# sch.net
KiCad netlist of a schematic drawn in Altium Designer
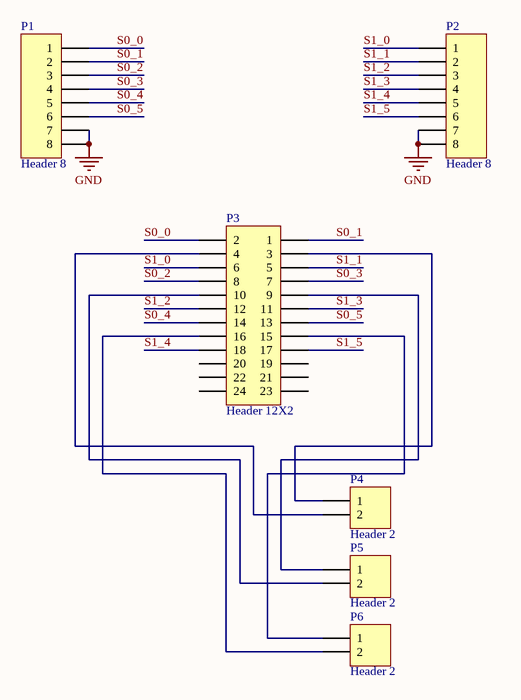
[diagram p0: sch.SchDoc]

(export (version "E")
  (design (tool "Eeschema 10.0.6"))
  (components
    (comp (ref "P1")
      (value "Header 8")
      (footprint "DS1102")
      (description "Header, 8-Pin")
      (fields (field (name "PUBLISHER") "Altium Limited"))
      (libsource (lib "Miscellaneous Connectors") (part "Header 8"))
    )
    (comp (ref "P2")
      (value "Header 8")
      (footprint "DS1102")
      (description "Header, 8-Pin")
      (fields (field (name "PUBLISHER") "Altium Limited"))
      (libsource (lib "") (part "Header 8_1"))
    )
    (comp (ref "P3")
      (value "Header 12X2")
      (footprint "P2K-8")
      (description "Header, 12-Pin, Dual row")
      (fields (field (name "PUBLISHER") "Altium Limited"))
      (libsource (lib "Miscellaneous Connectors") (part "Header 12X2"))
    )
    (comp (ref "P4")
      (value "Header 2")
      (footprint "HDR1X2")
      (description "Header, 2-Pin")
      (fields (field (name "PUBLISHER") "Altium Limited"))
      (libsource (lib "Miscellaneous Connectors") (part "Header 2"))
    )
    (comp (ref "P5")
      (value "Header 2")
      (footprint "HDR1X2")
      (description "Header, 2-Pin")
      (fields (field (name "PUBLISHER") "Altium Limited"))
      (libsource (lib "Miscellaneous Connectors") (part "Header 2"))
    )
    (comp (ref "P6")
      (value "Header 2")
      (footprint "HDR1X2")
      (description "Header, 2-Pin")
      (fields (field (name "PUBLISHER") "Altium Limited"))
      (libsource (lib "Miscellaneous Connectors") (part "Header 2"))
    )
  )
  (nets
    (net (code "1") (name "/S0_0") (class "Default")
      (node (ref "P1") (pin "1") (pinfunction "1_1") (pintype "passive"))
      (node (ref "P3") (pin "2") (pinfunction "2_2") (pintype "passive"))
    )
    (net (code "2") (name "/S0_1") (class "Default")
      (node (ref "P1") (pin "2") (pinfunction "2_2") (pintype "passive"))
      (node (ref "P3") (pin "1") (pinfunction "1_1") (pintype "passive"))
    )
    (net (code "3") (name "/S0_2") (class "Default")
      (node (ref "P1") (pin "3") (pinfunction "3_3") (pintype "passive"))
      (node (ref "P3") (pin "8") (pinfunction "8_8") (pintype "passive"))
    )
    (net (code "4") (name "/S0_3") (class "Default")
      (node (ref "P1") (pin "4") (pinfunction "4_4") (pintype "passive"))
      (node (ref "P3") (pin "7") (pinfunction "7_7") (pintype "passive"))
    )
    (net (code "5") (name "/S0_4") (class "Default")
      (node (ref "P1") (pin "5") (pinfunction "5_5") (pintype "passive"))
      (node (ref "P3") (pin "14") (pinfunction "14_14") (pintype "passive"))
    )
    (net (code "6") (name "/S0_5") (class "Default")
      (node (ref "P1") (pin "6") (pinfunction "6_6") (pintype "passive"))
      (node (ref "P3") (pin "13") (pinfunction "13_13") (pintype "passive"))
    )
    (net (code "7") (name "/S1_0") (class "Default")
      (node (ref "P2") (pin "1") (pinfunction "1_1") (pintype "passive"))
      (node (ref "P3") (pin "6") (pinfunction "6_6") (pintype "passive"))
    )
    (net (code "8") (name "/S1_1") (class "Default")
      (node (ref "P2") (pin "2") (pinfunction "2_2") (pintype "passive"))
      (node (ref "P3") (pin "5") (pinfunction "5_5") (pintype "passive"))
    )
    (net (code "9") (name "/S1_2") (class "Default")
      (node (ref "P2") (pin "3") (pinfunction "3_3") (pintype "passive"))
      (node (ref "P3") (pin "12") (pinfunction "12_12") (pintype "passive"))
    )
    (net (code "10") (name "/S1_3") (class "Default")
      (node (ref "P2") (pin "4") (pinfunction "4_4") (pintype "passive"))
      (node (ref "P3") (pin "11") (pinfunction "11_11") (pintype "passive"))
    )
    (net (code "11") (name "/S1_4") (class "Default")
      (node (ref "P2") (pin "5") (pinfunction "5_5") (pintype "passive"))
      (node (ref "P3") (pin "18") (pinfunction "18_18") (pintype "passive"))
    )
    (net (code "12") (name "/S1_5") (class "Default")
      (node (ref "P2") (pin "6") (pinfunction "6_6") (pintype "passive"))
      (node (ref "P3") (pin "17") (pinfunction "17_17") (pintype "passive"))
    )
    (net (code "13") (name "GND") (class "Default")
      (node (ref "P1") (pin "7") (pinfunction "7_7") (pintype "passive"))
      (node (ref "P1") (pin "8") (pinfunction "8_8") (pintype "passive"))
      (node (ref "P2") (pin "7") (pinfunction "7_7") (pintype "passive"))
      (node (ref "P2") (pin "8") (pinfunction "8_8") (pintype "passive"))
    )
    (net (code "14") (name "Net-(P3-Pad3)") (class "Default")
      (node (ref "P3") (pin "3") (pinfunction "3_3") (pintype "passive"))
      (node (ref "P4") (pin "1") (pinfunction "1_1") (pintype "passive"))
    )
    (net (code "15") (name "Net-(P3-Pad4)") (class "Default")
      (node (ref "P3") (pin "4") (pinfunction "4_4") (pintype "passive"))
      (node (ref "P4") (pin "2") (pinfunction "2_2") (pintype "passive"))
    )
    (net (code "16") (name "Net-(P3-Pad9)") (class "Default")
      (node (ref "P3") (pin "9") (pinfunction "9_9") (pintype "passive"))
      (node (ref "P5") (pin "1") (pinfunction "1_1") (pintype "passive"))
    )
    (net (code "17") (name "Net-(P3-Pad10)") (class "Default")
      (node (ref "P3") (pin "10") (pinfunction "10_10") (pintype "passive"))
      (node (ref "P5") (pin "2") (pinfunction "2_2") (pintype "passive"))
    )
    (net (code "18") (name "Net-(P3-Pad15)") (class "Default")
      (node (ref "P3") (pin "15") (pinfunction "15_15") (pintype "passive"))
      (node (ref "P6") (pin "1") (pinfunction "1_1") (pintype "passive"))
    )
    (net (code "19") (name "Net-(P3-Pad16)") (class "Default")
      (node (ref "P3") (pin "16") (pinfunction "16_16") (pintype "passive"))
      (node (ref "P6") (pin "2") (pinfunction "2_2") (pintype "passive"))
    )
    (net (code "20") (name "unconnected-(P3-Pad19)") (class "Default")
      (node (ref "P3") (pin "19") (pinfunction "19_19") (pintype "passive"))
    )
    (net (code "21") (name "unconnected-(P3-Pad20)") (class "Default")
      (node (ref "P3") (pin "20") (pinfunction "20_20") (pintype "passive"))
    )
    (net (code "22") (name "unconnected-(P3-Pad21)") (class "Default")
      (node (ref "P3") (pin "21") (pinfunction "21_21") (pintype "passive"))
    )
    (net (code "23") (name "unconnected-(P3-Pad22)") (class "Default")
      (node (ref "P3") (pin "22") (pinfunction "22_22") (pintype "passive"))
    )
    (net (code "24") (name "unconnected-(P3-Pad23)") (class "Default")
      (node (ref "P3") (pin "23") (pinfunction "23_23") (pintype "passive"))
    )
    (net (code "25") (name "unconnected-(P3-Pad24)") (class "Default")
      (node (ref "P3") (pin "24") (pinfunction "24_24") (pintype "passive"))
    )
  )
)
